# ethernet-phy.net
KiCad netlist of a schematic drawn in Altium Designer
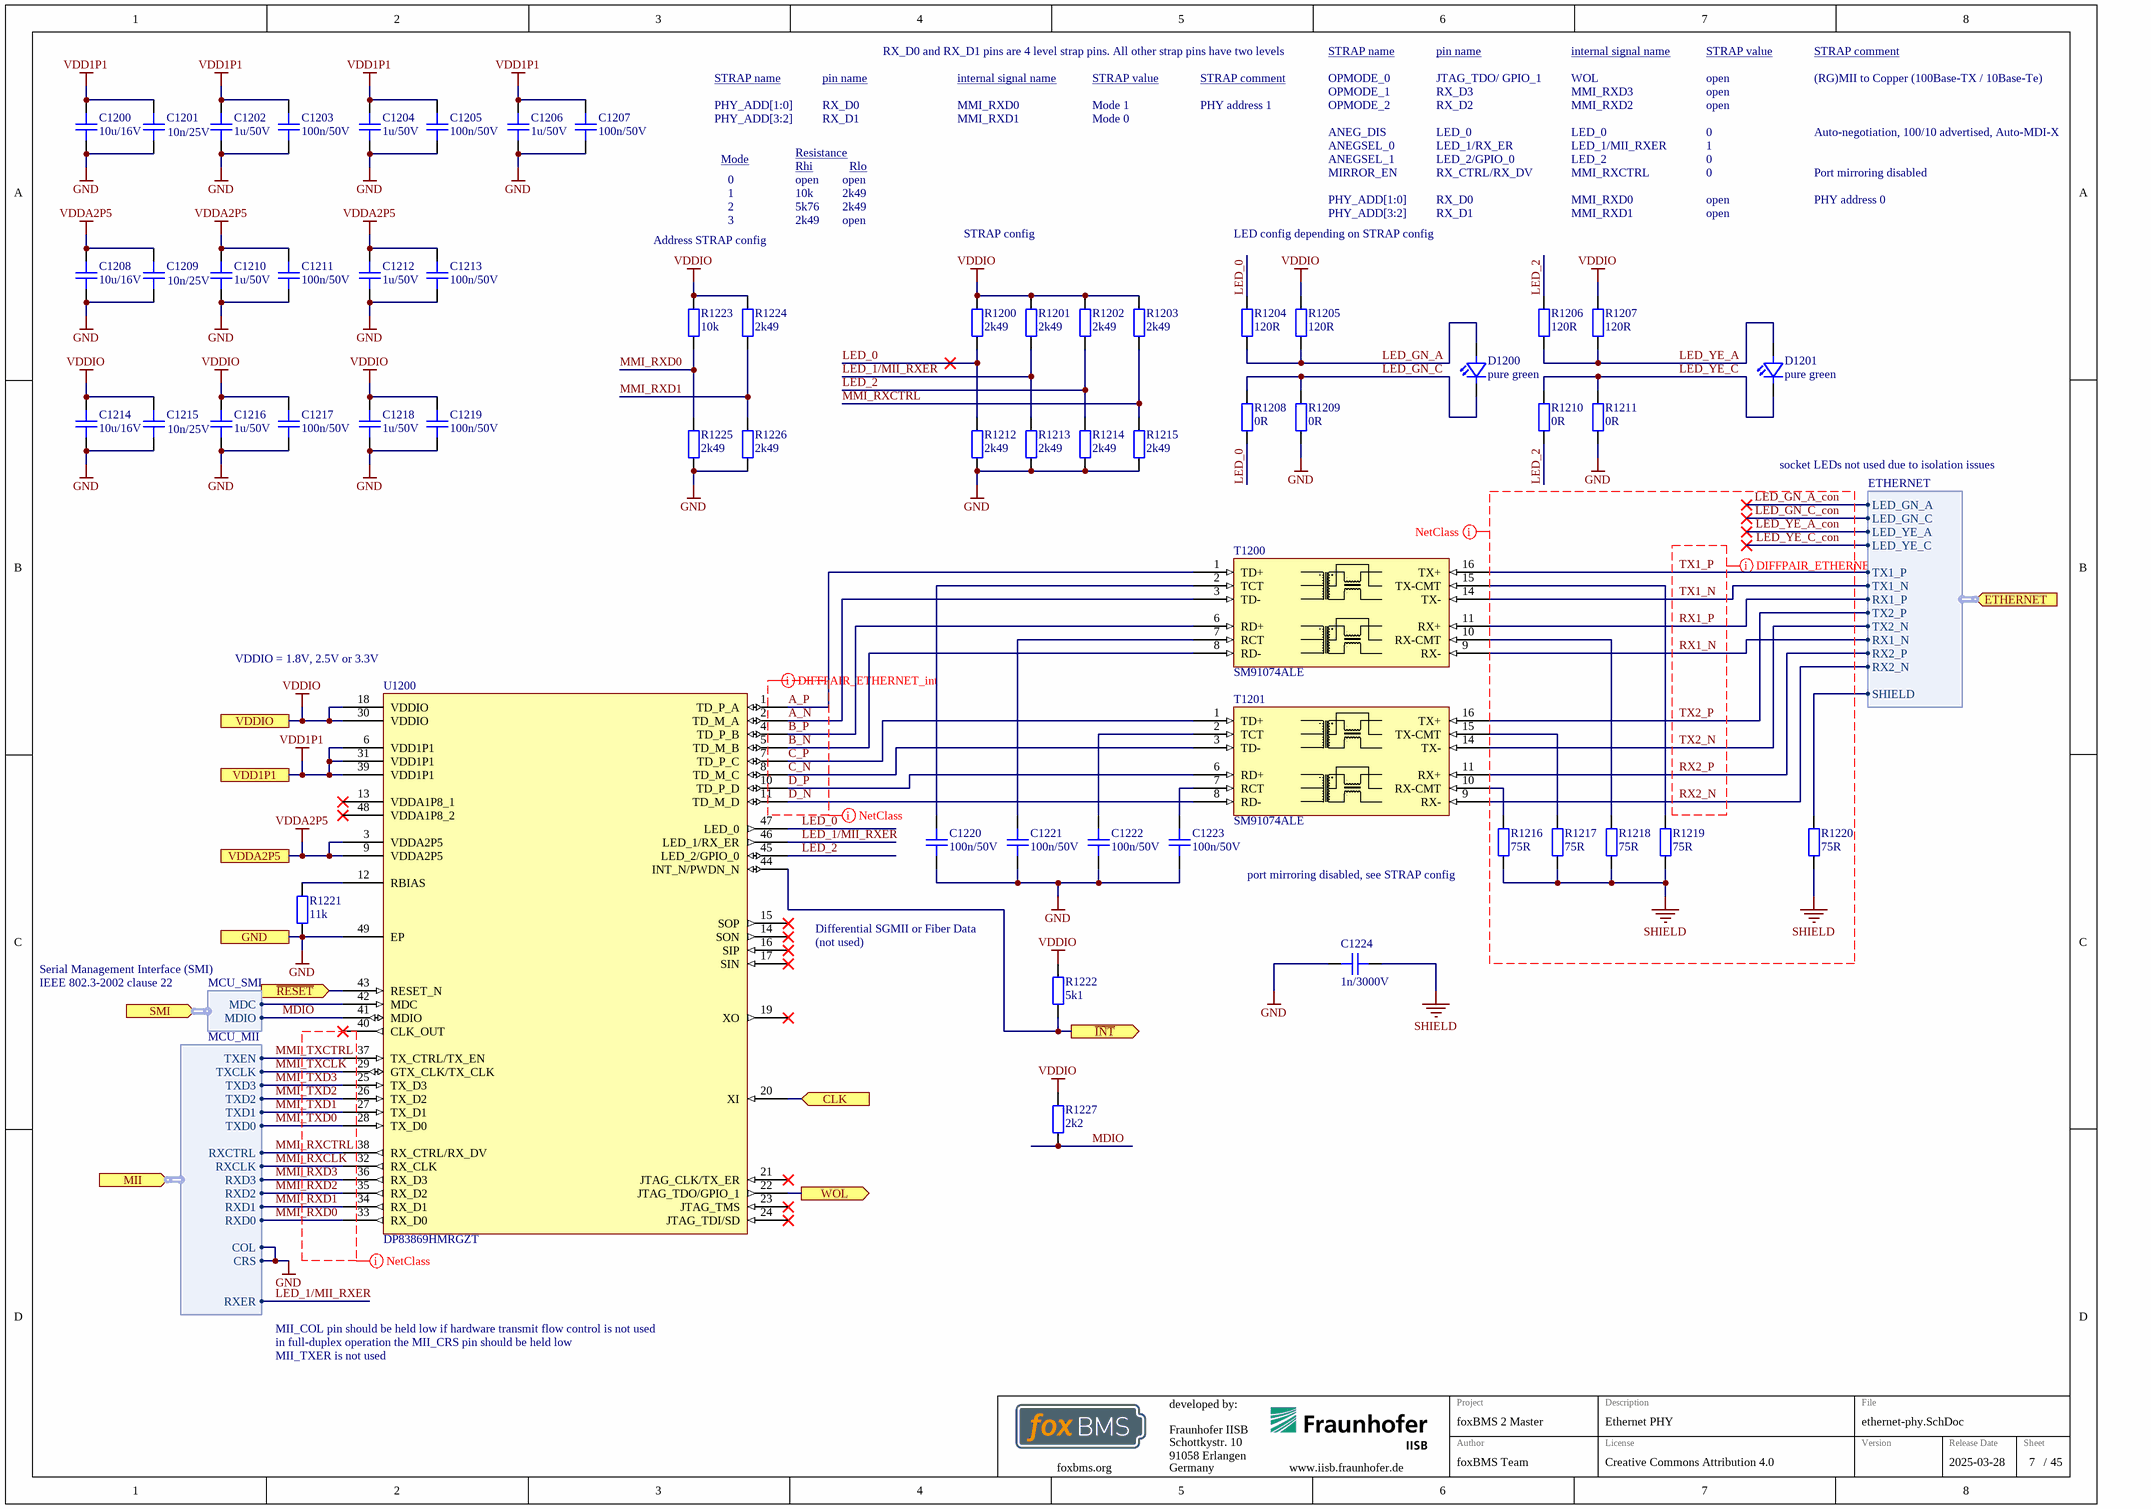
[diagram p0: ethernet-phy.SchDoc]

(export (version "E")
  (design (tool "Eeschema 10.0.6"))
  (components
    (comp (ref "C1200")
      (value "10u/16V")
      (footprint "CAPC2012X14N")
      (description "MLCC")
      (fields (field (name "PART NUMBER") "gen_C_ceramic_10u_16V_X7R_0805"))
      (libsource (lib "OE750") (part "C"))
    )
    (comp (ref "C1201")
      (value "10n/25V")
      (footprint "CAPC1005X06N")
      (description "MLCC")
      (fields (field (name "PART NUMBER") "gen_C_ceramic_10n_25V_X7R_0402"))
      (libsource (lib "OE750") (part "C"))
    )
    (comp (ref "C1202")
      (value "1u/50V")
      (footprint "CAPC1608X08N")
      (description "MLCC")
      (fields (field (name "PART NUMBER") "gen_C_ceramic_1u_50V_X7R_0603") (field (name "TOLERANCE") "± 10%"))
      (libsource (lib "OE750") (part "C"))
    )
    (comp (ref "C1203")
      (value "100n/50V")
      (footprint "CAPC1005X06N")
      (description "MLCC")
      (fields (field (name "PART NUMBER") "gen_C_ceramic_100n_50V_X7R_0402"))
      (libsource (lib "OE750") (part "C"))
    )
    (comp (ref "C1204")
      (value "1u/50V")
      (footprint "CAPC1608X08N")
      (description "MLCC")
      (fields (field (name "PART NUMBER") "gen_C_ceramic_1u_50V_X7R_0603") (field (name "TOLERANCE") "± 10%"))
      (libsource (lib "OE750") (part "C"))
    )
    (comp (ref "C1205")
      (value "100n/50V")
      (footprint "CAPC1005X06N")
      (description "MLCC")
      (fields (field (name "PART NUMBER") "gen_C_ceramic_100n_50V_X7R_0402"))
      (libsource (lib "OE750") (part "C"))
    )
    (comp (ref "C1206")
      (value "1u/50V")
      (footprint "CAPC1608X08N")
      (description "MLCC")
      (fields (field (name "PART NUMBER") "gen_C_ceramic_1u_50V_X7R_0603") (field (name "TOLERANCE") "± 10%"))
      (libsource (lib "OE750") (part "C"))
    )
    (comp (ref "C1207")
      (value "100n/50V")
      (footprint "CAPC1005X06N")
      (description "MLCC")
      (fields (field (name "PART NUMBER") "gen_C_ceramic_100n_50V_X7R_0402"))
      (libsource (lib "OE750") (part "C"))
    )
    (comp (ref "C1208")
      (value "10u/16V")
      (footprint "CAPC2012X14N")
      (description "MLCC")
      (fields (field (name "PART NUMBER") "gen_C_ceramic_10u_16V_X7R_0805"))
      (libsource (lib "OE750") (part "C"))
    )
    (comp (ref "C1209")
      (value "10n/25V")
      (footprint "CAPC1005X06N")
      (description "MLCC")
      (fields (field (name "PART NUMBER") "gen_C_ceramic_10n_25V_X7R_0402"))
      (libsource (lib "OE750") (part "C"))
    )
    (comp (ref "C1210")
      (value "1u/50V")
      (footprint "CAPC1608X08N")
      (description "MLCC")
      (fields (field (name "PART NUMBER") "gen_C_ceramic_1u_50V_X7R_0603") (field (name "TOLERANCE") "± 10%"))
      (libsource (lib "OE750") (part "C"))
    )
    (comp (ref "C1211")
      (value "100n/50V")
      (footprint "CAPC1005X06N")
      (description "MLCC")
      (fields (field (name "PART NUMBER") "gen_C_ceramic_100n_50V_X7R_0402"))
      (libsource (lib "OE750") (part "C"))
    )
    (comp (ref "C1212")
      (value "1u/50V")
      (footprint "CAPC1608X08N")
      (description "MLCC")
      (fields (field (name "PART NUMBER") "gen_C_ceramic_1u_50V_X7R_0603") (field (name "TOLERANCE") "± 10%"))
      (libsource (lib "OE750") (part "C"))
    )
    (comp (ref "C1213")
      (value "100n/50V")
      (footprint "CAPC1005X06N")
      (description "MLCC")
      (fields (field (name "PART NUMBER") "gen_C_ceramic_100n_50V_X7R_0402"))
      (libsource (lib "OE750") (part "C"))
    )
    (comp (ref "C1214")
      (value "10u/16V")
      (footprint "CAPC2012X14N")
      (description "MLCC")
      (fields (field (name "PART NUMBER") "gen_C_ceramic_10u_16V_X7R_0805"))
      (libsource (lib "OE750") (part "C"))
    )
    (comp (ref "C1215")
      (value "10n/25V")
      (footprint "CAPC1005X06N")
      (description "MLCC")
      (fields (field (name "PART NUMBER") "gen_C_ceramic_10n_25V_X7R_0402"))
      (libsource (lib "OE750") (part "C"))
    )
    (comp (ref "C1216")
      (value "1u/50V")
      (footprint "CAPC1608X08N")
      (description "MLCC")
      (fields (field (name "PART NUMBER") "gen_C_ceramic_1u_50V_X7R_0603") (field (name "TOLERANCE") "± 10%"))
      (libsource (lib "OE750") (part "C"))
    )
    (comp (ref "C1217")
      (value "100n/50V")
      (footprint "CAPC1005X06N")
      (description "MLCC")
      (fields (field (name "PART NUMBER") "gen_C_ceramic_100n_50V_X7R_0402"))
      (libsource (lib "OE750") (part "C"))
    )
    (comp (ref "C1218")
      (value "1u/50V")
      (footprint "CAPC1608X08N")
      (description "MLCC")
      (fields (field (name "PART NUMBER") "gen_C_ceramic_1u_50V_X7R_0603") (field (name "TOLERANCE") "± 10%"))
      (libsource (lib "OE750") (part "C"))
    )
    (comp (ref "C1219")
      (value "100n/50V")
      (footprint "CAPC1005X06N")
      (description "MLCC")
      (fields (field (name "PART NUMBER") "gen_C_ceramic_100n_50V_X7R_0402"))
      (libsource (lib "OE750") (part "C"))
    )
    (comp (ref "C1220")
      (value "100n/50V")
      (footprint "CAPC1005X06N")
      (description "MLCC")
      (fields (field (name "PART NUMBER") "gen_C_ceramic_100n_50V_X7R_0402"))
      (libsource (lib "OE750") (part "C"))
    )
    (comp (ref "C1221")
      (value "100n/50V")
      (footprint "CAPC1005X06N")
      (description "MLCC")
      (fields (field (name "PART NUMBER") "gen_C_ceramic_100n_50V_X7R_0402"))
      (libsource (lib "OE750") (part "C"))
    )
    (comp (ref "C1222")
      (value "100n/50V")
      (footprint "CAPC1005X06N")
      (description "MLCC")
      (fields (field (name "PART NUMBER") "gen_C_ceramic_100n_50V_X7R_0402"))
      (libsource (lib "OE750") (part "C"))
    )
    (comp (ref "C1223")
      (value "100n/50V")
      (footprint "CAPC1005X06N")
      (description "MLCC")
      (fields (field (name "PART NUMBER") "gen_C_ceramic_100n_50V_X7R_0402"))
      (libsource (lib "OE750") (part "C"))
    )
    (comp (ref "C1224")
      (value "1n/3000V")
      (footprint "CAPC2220(5750)230_N")
      (description "MLCC")
      (fields (field (name "PART NUMBER") "gen_C_ceramic_1n_3000V_X7R_2220"))
      (libsource (lib "OE750") (part "C"))
    )
    (comp (ref "D1200")
      (value "pure green")
      (footprint "LEDC1608X07N")
      (description "TLMP1100-GS08")
      (fields (field (name "PART NUMBER") "LED_0603_pure_green_AECQ") (field (name "MANUFACTURER") "Vishay"))
      (libsource (lib "OE750") (part "D_LED"))
    )
    (comp (ref "D1201")
      (value "pure green")
      (footprint "LEDC1608X07N")
      (description "TLMP1100-GS08")
      (fields (field (name "PART NUMBER") "LED_0603_pure_green_AECQ") (field (name "MANUFACTURER") "Vishay"))
      (libsource (lib "OE750") (part "D_LED"))
    )
    (comp (ref "R1200")
      (value "2k49")
      (footprint "RESC1005X04N")
      (description "SMD Resistor 2k49 0402")
      (fields (field (name "PART NUMBER") "gen_R_2k49_0402") (field (name "TOLERANCE") "1%"))
      (libsource (lib "OE750") (part "R"))
    )
    (comp (ref "R1201")
      (value "2k49")
      (footprint "RESC1005X04N")
      (description "SMD Resistor 2k49 0402")
      (fields (field (name "PART NUMBER") "gen_R_2k49_0402") (field (name "TOLERANCE") "1%"))
      (libsource (lib "OE750") (part "R"))
    )
    (comp (ref "R1202")
      (value "2k49")
      (footprint "RESC1005X04N")
      (description "SMD Resistor 2k49 0402")
      (fields (field (name "PART NUMBER") "gen_R_2k49_0402") (field (name "TOLERANCE") "1%"))
      (libsource (lib "OE750") (part "R"))
    )
    (comp (ref "R1203")
      (value "2k49")
      (footprint "RESC1005X04N")
      (description "SMD Resistor 2k49 0402")
      (fields (field (name "PART NUMBER") "gen_R_2k49_0402") (field (name "TOLERANCE") "1%"))
      (libsource (lib "OE750") (part "R"))
    )
    (comp (ref "R1204")
      (value "120R")
      (footprint "RESC1005X04N")
      (description "SMD Resistor 120R 0402")
      (fields (field (name "PART NUMBER") "gen_R_120R_0402") (field (name "TOLERANCE") "1%"))
      (libsource (lib "OE750") (part "R"))
    )
    (comp (ref "R1205")
      (value "120R")
      (footprint "RESC1005X04N")
      (description "SMD Resistor 120R 0402")
      (fields (field (name "PART NUMBER") "gen_R_120R_0402") (field (name "TOLERANCE") "1%"))
      (libsource (lib "OE750") (part "R"))
    )
    (comp (ref "R1206")
      (value "120R")
      (footprint "RESC1005X04N")
      (description "SMD Resistor 120R 0402")
      (fields (field (name "PART NUMBER") "gen_R_120R_0402") (field (name "TOLERANCE") "1%"))
      (libsource (lib "OE750") (part "R"))
    )
    (comp (ref "R1207")
      (value "120R")
      (footprint "RESC1005X04N")
      (description "SMD Resistor 120R 0402")
      (fields (field (name "PART NUMBER") "gen_R_120R_0402") (field (name "TOLERANCE") "1%"))
      (libsource (lib "OE750") (part "R"))
    )
    (comp (ref "R1208")
      (value "0R")
      (footprint "RESC1005X04N")
      (description "SMD Resistor 0R 0402")
      (fields (field (name "PART NUMBER") "gen_R_0R_0402") (field (name "POWER") "0.063W"))
      (libsource (lib "OE750") (part "R"))
    )
    (comp (ref "R1209")
      (value "0R")
      (footprint "RESC1005X04N")
      (description "SMD Resistor 0R 0402")
      (fields (field (name "PART NUMBER") "gen_R_0R_0402") (field (name "POWER") "0.063W"))
      (libsource (lib "OE750") (part "R"))
    )
    (comp (ref "R1210")
      (value "0R")
      (footprint "RESC1005X04N")
      (description "SMD Resistor 0R 0402")
      (fields (field (name "PART NUMBER") "gen_R_0R_0402") (field (name "POWER") "0.063W"))
      (libsource (lib "OE750") (part "R"))
    )
    (comp (ref "R1211")
      (value "0R")
      (footprint "RESC1005X04N")
      (description "SMD Resistor 0R 0402")
      (fields (field (name "PART NUMBER") "gen_R_0R_0402") (field (name "POWER") "0.063W"))
      (libsource (lib "OE750") (part "R"))
    )
    (comp (ref "R1212")
      (value "2k49")
      (footprint "RESC1005X04N")
      (description "SMD Resistor 2k49 0402")
      (fields (field (name "PART NUMBER") "gen_R_2k49_0402") (field (name "TOLERANCE") "1%"))
      (libsource (lib "OE750") (part "R"))
    )
    (comp (ref "R1213")
      (value "2k49")
      (footprint "RESC1005X04N")
      (description "SMD Resistor 2k49 0402")
      (fields (field (name "PART NUMBER") "gen_R_2k49_0402") (field (name "TOLERANCE") "1%"))
      (libsource (lib "OE750") (part "R"))
    )
    (comp (ref "R1214")
      (value "2k49")
      (footprint "RESC1005X04N")
      (description "SMD Resistor 2k49 0402")
      (fields (field (name "PART NUMBER") "gen_R_2k49_0402") (field (name "TOLERANCE") "1%"))
      (libsource (lib "OE750") (part "R"))
    )
    (comp (ref "R1215")
      (value "2k49")
      (footprint "RESC1005X04N")
      (description "SMD Resistor 2k49 0402")
      (fields (field (name "PART NUMBER") "gen_R_2k49_0402") (field (name "TOLERANCE") "1%"))
      (libsource (lib "OE750") (part "R"))
    )
    (comp (ref "R1216")
      (value "75R")
      (footprint "RESC1005X04N")
      (description "SMD Resistor 75R 0402")
      (fields (field (name "PART NUMBER") "gen_R_75R_0402") (field (name "TOLERANCE") "1%"))
      (libsource (lib "OE750") (part "R"))
    )
    (comp (ref "R1217")
      (value "75R")
      (footprint "RESC1005X04N")
      (description "SMD Resistor 75R 0402")
      (fields (field (name "PART NUMBER") "gen_R_75R_0402") (field (name "TOLERANCE") "1%"))
      (libsource (lib "OE750") (part "R"))
    )
    (comp (ref "R1218")
      (value "75R")
      (footprint "RESC1005X04N")
      (description "SMD Resistor 75R 0402")
      (fields (field (name "PART NUMBER") "gen_R_75R_0402") (field (name "TOLERANCE") "1%"))
      (libsource (lib "OE750") (part "R"))
    )
    (comp (ref "R1219")
      (value "75R")
      (footprint "RESC1005X04N")
      (description "SMD Resistor 75R 0402")
      (fields (field (name "PART NUMBER") "gen_R_75R_0402") (field (name "TOLERANCE") "1%"))
      (libsource (lib "OE750") (part "R"))
    )
    (comp (ref "R1220")
      (value "75R")
      (footprint "RESC1005X04N")
      (description "SMD Resistor 75R 0402")
      (fields (field (name "PART NUMBER") "gen_R_75R_0402") (field (name "TOLERANCE") "1%"))
      (libsource (lib "OE750") (part "R"))
    )
    (comp (ref "R1221")
      (value "11k")
      (footprint "RESC1005X04N")
      (description "SMD Resistor 11k 0402")
      (fields (field (name "PART NUMBER") "gen_R_11k_0402") (field (name "TOLERANCE") "1%"))
      (libsource (lib "OE750") (part "R"))
    )
    (comp (ref "R1222")
      (value "5k1")
      (footprint "RESC1005X04N")
      (description "SMD Resistor 5k1 0402")
      (fields (field (name "PART NUMBER") "gen_R_5k1_0402") (field (name "TOLERANCE") "1%"))
      (libsource (lib "OE750") (part "R"))
    )
    (comp (ref "R1223")
      (value "10k")
      (footprint "RESC1005X04N")
      (description "SMD Resistor 10k 0402")
      (fields (field (name "PART NUMBER") "gen_R_10k_0402") (field (name "TOLERANCE") "1%"))
      (libsource (lib "OE750") (part "R"))
    )
    (comp (ref "R1224")
      (value "2k49")
      (footprint "RESC1005X04N")
      (description "SMD Resistor 2k49 0402")
      (fields (field (name "PART NUMBER") "gen_R_2k49_0402") (field (name "TOLERANCE") "1%"))
      (libsource (lib "OE750") (part "R"))
    )
    (comp (ref "R1225")
      (value "2k49")
      (footprint "RESC1005X04N")
      (description "SMD Resistor 2k49 0402")
      (fields (field (name "PART NUMBER") "gen_R_2k49_0402") (field (name "TOLERANCE") "1%"))
      (libsource (lib "OE750") (part "R"))
    )
    (comp (ref "R1226")
      (value "2k49")
      (footprint "RESC1005X04N")
      (description "SMD Resistor 2k49 0402")
      (fields (field (name "PART NUMBER") "gen_R_2k49_0402") (field (name "TOLERANCE") "1%"))
      (libsource (lib "OE750") (part "R"))
    )
    (comp (ref "R1227")
      (value "2k2")
      (footprint "RESC1005X04N")
      (description "SMD Resistor 2k2 0402")
      (fields (field (name "PART NUMBER") "gen_R_2k2_0402") (field (name "TOLERANCE") "1%"))
      (libsource (lib "OE750") (part "R"))
    )
    (comp (ref "T1200")
      (value "SM91074ALE")
      (footprint "SM91074ALE")
      (description "10/100 Base-T Transformer")
      (fields (field (name "MANUFACTURER") "Bourns"))
      (libsource (lib "OE750") (part "SM91074ALE"))
    )
    (comp (ref "T1201")
      (value "SM91074ALE")
      (footprint "SM91074ALE")
      (description "10/100 Base-T Transformer")
      (fields (field (name "MANUFACTURER") "Bourns"))
      (libsource (lib "OE750") (part "SM91074ALE"))
    )
    (comp (ref "U1200")
      (value "DP83869HMRGZT")
      (footprint "DP83869HM-RGZ")
      (description "High Immunity 10/100/1000 Ethernet Physical Layer Transceiver and Fiber Interface")
      (fields (field (name "MANUFACTURER") "Texas Instruments"))
      (libsource (lib "OE750") (part "DP83869HM"))
    )
  )
  (nets
    (net (code "4") (name "/A_N") (class "Default")
      (node (ref "T1200") (pin "3") (pinfunction "TD-_3") (pintype "input"))
      (node (ref "U1200") (pin "2") (pinfunction "TD_M_A_2") (pintype "bidirectional"))
    )
    (net (code "5") (name "/A_P") (class "Default")
      (node (ref "T1200") (pin "1") (pinfunction "TD+_1") (pintype "input"))
      (node (ref "U1200") (pin "1") (pinfunction "TD_P_A_1") (pintype "bidirectional"))
    )
    (net (code "6") (name "/B_N") (class "Default")
      (node (ref "T1200") (pin "8") (pinfunction "RD-_8") (pintype "input"))
      (node (ref "U1200") (pin "5") (pinfunction "TD_M_B_5") (pintype "bidirectional"))
    )
    (net (code "7") (name "/B_P") (class "Default")
      (node (ref "T1200") (pin "6") (pinfunction "RD+_6") (pintype "input"))
      (node (ref "U1200") (pin "4") (pinfunction "TD_P_B_4") (pintype "bidirectional"))
    )
    (net (code "8") (name "/CLK") (class "Default")
      (node (ref "U1200") (pin "20") (pinfunction "XI_20") (pintype "input"))
    )
    (net (code "9") (name "/C_N") (class "Default")
      (node (ref "T1201") (pin "3") (pinfunction "TD-_3") (pintype "input"))
      (node (ref "U1200") (pin "8") (pinfunction "TD_M_C_8") (pintype "bidirectional"))
    )
    (net (code "10") (name "/C_P") (class "Default")
      (node (ref "T1201") (pin "1") (pinfunction "TD+_1") (pintype "input"))
      (node (ref "U1200") (pin "7") (pinfunction "TD_P_C_7") (pintype "bidirectional"))
    )
    (net (code "11") (name "/D_N") (class "Default")
      (node (ref "T1201") (pin "8") (pinfunction "RD-_8") (pintype "input"))
      (node (ref "U1200") (pin "11") (pinfunction "TD_M_D_11") (pintype "bidirectional"))
    )
    (net (code "12") (name "/D_P") (class "Default")
      (node (ref "T1201") (pin "6") (pinfunction "RD+_6") (pintype "input"))
      (node (ref "U1200") (pin "10") (pinfunction "TD_P_D_10") (pintype "bidirectional"))
    )
    (net (code "13") (name "/INT") (class "Default")
      (node (ref "R1222") (pin "1") (pinfunction "1_1") (pintype "passive"))
      (node (ref "U1200") (pin "44") (pinfunction "INT_N/PWDN_N_44") (pintype "bidirectional"))
    )
    (net (code "14") (name "/LED_0") (class "Default")
      (node (ref "R1200") (pin "1") (pinfunction "1_1") (pintype "passive"))
      (node (ref "R1204") (pin "2") (pinfunction "2_2") (pintype "passive"))
      (node (ref "R1208") (pin "1") (pinfunction "1_1") (pintype "passive"))
      (node (ref "R1212") (pin "2") (pinfunction "2_2") (pintype "passive"))
      (node (ref "U1200") (pin "47") (pinfunction "LED_0_47") (pintype "output"))
    )
    (net (code "15") (name "/LED_1{slash}MII_RXER") (class "Default")
      (node (ref "R1201") (pin "1") (pinfunction "1_1") (pintype "passive"))
      (node (ref "R1213") (pin "2") (pinfunction "2_2") (pintype "passive"))
      (node (ref "U1200") (pin "46") (pinfunction "LED_1/RX_ER_46") (pintype "output"))
    )
    (net (code "16") (name "/LED_2") (class "Default")
      (node (ref "R1202") (pin "1") (pinfunction "1_1") (pintype "passive"))
      (node (ref "R1206") (pin "2") (pinfunction "2_2") (pintype "passive"))
      (node (ref "R1210") (pin "1") (pinfunction "1_1") (pintype "passive"))
      (node (ref "R1214") (pin "2") (pinfunction "2_2") (pintype "passive"))
      (node (ref "U1200") (pin "45") (pinfunction "LED_2/GPIO_0_45") (pintype "bidirectional"))
    )
    (net (code "17") (name "/LED_GN_A") (class "Default")
      (node (ref "D1200") (pin "2") (pinfunction "A_2") (pintype "passive"))
      (node (ref "R1204") (pin "1") (pinfunction "1_1") (pintype "passive"))
      (node (ref "R1205") (pin "1") (pinfunction "1_1") (pintype "passive"))
    )
    (net (code "19") (name "/LED_GN_C") (class "Default")
      (node (ref "D1200") (pin "1") (pinfunction "C_1") (pintype "passive"))
      (node (ref "R1208") (pin "2") (pinfunction "2_2") (pintype "passive"))
      (node (ref "R1209") (pin "2") (pinfunction "2_2") (pintype "passive"))
    )
    (net (code "21") (name "/LED_YE_A") (class "Default")
      (node (ref "D1201") (pin "2") (pinfunction "A_2") (pintype "passive"))
      (node (ref "R1206") (pin "1") (pinfunction "1_1") (pintype "passive"))
      (node (ref "R1207") (pin "1") (pinfunction "1_1") (pintype "passive"))
    )
    (net (code "23") (name "/LED_YE_C") (class "Default")
      (node (ref "D1201") (pin "1") (pinfunction "C_1") (pintype "passive"))
      (node (ref "R1210") (pin "2") (pinfunction "2_2") (pintype "passive"))
      (node (ref "R1211") (pin "2") (pinfunction "2_2") (pintype "passive"))
    )
    (net (code "25") (name "/MDC") (class "Default")
      (node (ref "U1200") (pin "42") (pinfunction "MDC_42") (pintype "input"))
    )
    (net (code "26") (name "/MDIO") (class "Default")
      (node (ref "R1227") (pin "1") (pinfunction "1_1") (pintype "passive"))
      (node (ref "U1200") (pin "41") (pinfunction "MDIO_41") (pintype "bidirectional"))
    )
    (net (code "27") (name "/MMI_RXCLK") (class "Default")
      (node (ref "U1200") (pin "32") (pinfunction "RX_CLK_32") (pintype "output"))
    )
    (net (code "28") (name "/MMI_RXCTRL") (class "Default")
      (node (ref "R1203") (pin "1") (pinfunction "1_1") (pintype "passive"))
      (node (ref "R1215") (pin "2") (pinfunction "2_2") (pintype "passive"))
      (node (ref "U1200") (pin "38") (pinfunction "RX_CTRL/RX_DV_38") (pintype "output"))
    )
    (net (code "29") (name "/MMI_RXD0") (class "Default")
      (node (ref "R1223") (pin "1") (pinfunction "1_1") (pintype "passive"))
      (node (ref "R1225") (pin "2") (pinfunction "2_2") (pintype "passive"))
      (node (ref "U1200") (pin "33") (pinfunction "RX_D0_33") (pintype "output"))
    )
    (net (code "30") (name "/MMI_RXD1") (class "Default")
      (node (ref "R1224") (pin "1") (pinfunction "1_1") (pintype "passive"))
      (node (ref "R1226") (pin "2") (pinfunction "2_2") (pintype "passive"))
      (node (ref "U1200") (pin "34") (pinfunction "RX_D1_34") (pintype "output"))
    )
    (net (code "31") (name "/MMI_RXD2") (class "Default")
      (node (ref "U1200") (pin "35") (pinfunction "RX_D2_35") (pintype "output"))
    )
    (net (code "32") (name "/MMI_RXD3") (class "Default")
      (node (ref "U1200") (pin "36") (pinfunction "RX_D3_36") (pintype "output"))
    )
    (net (code "33") (name "/MMI_TXCLK") (class "Default")
      (node (ref "U1200") (pin "29") (pinfunction "GTX_CLK/TX_CLK_29") (pintype "bidirectional"))
    )
    (net (code "34") (name "/MMI_TXCTRL") (class "Default")
      (node (ref "U1200") (pin "37") (pinfunction "TX_CTRL/TX_EN_37") (pintype "input"))
    )
    (net (code "35") (name "/MMI_TXD0") (class "Default")
      (node (ref "U1200") (pin "28") (pinfunction "TX_D0_28") (pintype "input"))
    )
    (net (code "36") (name "/MMI_TXD1") (class "Default")
      (node (ref "U1200") (pin "27") (pinfunction "TX_D1_27") (pintype "input"))
    )
    (net (code "37") (name "/MMI_TXD2") (class "Default")
      (node (ref "U1200") (pin "26") (pinfunction "TX_D2_26") (pintype "input"))
    )
    (net (code "38") (name "/MMI_TXD3") (class "Default")
      (node (ref "U1200") (pin "25") (pinfunction "TX_D3_25") (pintype "input"))
    )
    (net (code "39") (name "/RESET") (class "Default")
      (node (ref "U1200") (pin "43") (pinfunction "RESET_N_43") (pintype "input"))
    )
    (net (code "40") (name "/RX1_N") (class "Default")
      (node (ref "T1200") (pin "9") (pinfunction "RX-_9") (pintype "input"))
    )
    (net (code "41") (name "/RX1_P") (class "Default")
      (node (ref "T1200") (pin "11") (pinfunction "RX+_11") (pintype "input"))
    )
    (net (code "42") (name "/RX2_N") (class "Default")
      (node (ref "T1201") (pin "9") (pinfunction "RX-_9") (pintype "input"))
    )
    (net (code "43") (name "/RX2_P") (class "Default")
      (node (ref "T1201") (pin "11") (pinfunction "RX+_11") (pintype "input"))
    )
    (net (code "44") (name "/TX1_N") (class "Default")
      (node (ref "T1200") (pin "14") (pinfunction "TX-_14") (pintype "input"))
    )
    (net (code "45") (name "/TX1_P") (class "Default")
      (node (ref "T1200") (pin "16") (pinfunction "TX+_16") (pintype "input"))
    )
    (net (code "46") (name "/TX2_N") (class "Default")
      (node (ref "T1201") (pin "14") (pinfunction "TX-_14") (pintype "input"))
    )
    (net (code "47") (name "/TX2_P") (class "Default")
      (node (ref "T1201") (pin "16") (pinfunction "TX+_16") (pintype "input"))
    )
    (net (code "48") (name "/WOL") (class "Default")
      (node (ref "U1200") (pin "22") (pinfunction "JTAG_TDO/GPIO_1_22") (pintype "output"))
    )
    (net (code "52") (name "GND") (class "Default")
      (node (ref "C1200") (pin "1") (pinfunction "1_1") (pintype "passive"))
      (node (ref "C1201") (pin "1") (pinfunction "1_1") (pintype "passive"))
      (node (ref "C1202") (pin "1") (pinfunction "1_1") (pintype "passive"))
      (node (ref "C1203") (pin "1") (pinfunction "1_1") (pintype "passive"))
      (node (ref "C1204") (pin "1") (pinfunction "1_1") (pintype "passive"))
      (node (ref "C1205") (pin "1") (pinfunction "1_1") (pintype "passive"))
      (node (ref "C1206") (pin "1") (pinfunction "1_1") (pintype "passive"))
      (node (ref "C1207") (pin "1") (pinfunction "1_1") (pintype "passive"))
      (node (ref "C1208") (pin "1") (pinfunction "1_1") (pintype "passive"))
      (node (ref "C1209") (pin "1") (pinfunction "1_1") (pintype "passive"))
      (node (ref "C1210") (pin "1") (pinfunction "1_1") (pintype "passive"))
      (node (ref "C1211") (pin "1") (pinfunction "1_1") (pintype "passive"))
      (node (ref "C1212") (pin "1") (pinfunction "1_1") (pintype "passive"))
      (node (ref "C1213") (pin "1") (pinfunction "1_1") (pintype "passive"))
      (node (ref "C1214") (pin "1") (pinfunction "1_1") (pintype "passive"))
      (node (ref "C1215") (pin "1") (pinfunction "1_1") (pintype "passive"))
      (node (ref "C1216") (pin "1") (pinfunction "1_1") (pintype "passive"))
      (node (ref "C1217") (pin "1") (pinfunction "1_1") (pintype "passive"))
      (node (ref "C1218") (pin "1") (pinfunction "1_1") (pintype "passive"))
      (node (ref "C1219") (pin "1") (pinfunction "1_1") (pintype "passive"))
      (node (ref "C1220") (pin "1") (pinfunction "1_1") (pintype "passive"))
      (node (ref "C1221") (pin "1") (pinfunction "1_1") (pintype "passive"))
      (node (ref "C1222") (pin "1") (pinfunction "1_1") (pintype "passive"))
      (node (ref "C1223") (pin "1") (pinfunction "1_1") (pintype "passive"))
      (node (ref "C1224") (pin "1") (pinfunction "1_1") (pintype "passive"))
      (node (ref "R1209") (pin "1") (pinfunction "1_1") (pintype "passive"))
      (node (ref "R1211") (pin "1") (pinfunction "1_1") (pintype "passive"))
      (node (ref "R1212") (pin "1") (pinfunction "1_1") (pintype "passive"))
      (node (ref "R1213") (pin "1") (pinfunction "1_1") (pintype "passive"))
      (node (ref "R1214") (pin "1") (pinfunction "1_1") (pintype "passive"))
      (node (ref "R1215") (pin "1") (pinfunction "1_1") (pintype "passive"))
      (node (ref "R1221") (pin "1") (pinfunction "1_1") (pintype "passive"))
      (node (ref "R1225") (pin "1") (pinfunction "1_1") (pintype "passive"))
      (node (ref "R1226") (pin "1") (pinfunction "1_1") (pintype "passive"))
      (node (ref "U1200") (pin "49") (pinfunction "EP_49") (pintype "power_in"))
    )
    (net (code "53") (name "Net-(T1200-RCT)") (class "Default")
      (node (ref "C1221") (pin "2") (pinfunction "2_2") (pintype "passive"))
      (node (ref "T1200") (pin "7") (pinfunction "RCT_7") (pintype "input"))
    )
    (net (code "54") (name "Net-(T1200-RX-CMT)") (class "Default")
      (node (ref "R1218") (pin "2") (pinfunction "2_2") (pintype "passive"))
      (node (ref "T1200") (pin "10") (pinfunction "RX-CMT_10") (pintype "input"))
    )
    (net (code "55") (name "Net-(T1200-TCT)") (class "Default")
      (node (ref "C1220") (pin "2") (pinfunction "2_2") (pintype "passive"))
      (node (ref "T1200") (pin "2") (pinfunction "TCT_2") (pintype "input"))
    )
    (net (code "56") (name "Net-(T1200-TX-CMT)") (class "Default")
      (node (ref "R1219") (pin "2") (pinfunction "2_2") (pintype "passive"))
      (node (ref "T1200") (pin "15") (pinfunction "TX-CMT_15") (pintype "input"))
    )
    (net (code "57") (name "Net-(T1201-RCT)") (class "Default")
      (node (ref "C1223") (pin "2") (pinfunction "2_2") (pintype "passive"))
      (node (ref "T1201") (pin "7") (pinfunction "RCT_7") (pintype "input"))
    )
    (net (code "58") (name "Net-(T1201-RX-CMT)") (class "Default")
      (node (ref "R1216") (pin "2") (pinfunction "2_2") (pintype "passive"))
      (node (ref "T1201") (pin "10") (pinfunction "RX-CMT_10") (pintype "input"))
    )
    (net (code "59") (name "Net-(T1201-TCT)") (class "Default")
      (node (ref "C1222") (pin "2") (pinfunction "2_2") (pintype "passive"))
      (node (ref "T1201") (pin "2") (pinfunction "TCT_2") (pintype "input"))
    )
    (net (code "60") (name "Net-(T1201-TX-CMT)") (class "Default")
      (node (ref "R1217") (pin "2") (pinfunction "2_2") (pintype "passive"))
      (node (ref "T1201") (pin "15") (pinfunction "TX-CMT_15") (pintype "input"))
    )
    (net (code "61") (name "Net-(U1200-RBIAS)") (class "Default")
      (node (ref "R1221") (pin "2") (pinfunction "2_2") (pintype "passive"))
      (node (ref "U1200") (pin "12") (pinfunction "RBIAS_12") (pintype "passive"))
    )
    (net (code "62") (name "SHIELD") (class "Default")
      (node (ref "C1224") (pin "2") (pinfunction "2_2") (pintype "passive"))
      (node (ref "R1216") (pin "1") (pinfunction "1_1") (pintype "passive"))
      (node (ref "R1217") (pin "1") (pinfunction "1_1") (pintype "passive"))
      (node (ref "R1218") (pin "1") (pinfunction "1_1") (pintype "passive"))
      (node (ref "R1219") (pin "1") (pinfunction "1_1") (pintype "passive"))
      (node (ref "R1220") (pin "1") (pinfunction "1_1") (pintype "passive"))
    )
    (net (code "63") (name "VDD1P1") (class "Default")
      (node (ref "C1200") (pin "2") (pinfunction "2_2") (pintype "passive"))
      (node (ref "C1201") (pin "2") (pinfunction "2_2") (pintype "passive"))
      (node (ref "C1202") (pin "2") (pinfunction "2_2") (pintype "passive"))
      (node (ref "C1203") (pin "2") (pinfunction "2_2") (pintype "passive"))
      (node (ref "C1204") (pin "2") (pinfunction "2_2") (pintype "passive"))
      (node (ref "C1205") (pin "2") (pinfunction "2_2") (pintype "passive"))
      (node (ref "C1206") (pin "2") (pinfunction "2_2") (pintype "passive"))
      (node (ref "C1207") (pin "2") (pinfunction "2_2") (pintype "passive"))
      (node (ref "U1200") (pin "31") (pinfunction "VDD1P1_31") (pintype "power_in"))
      (node (ref "U1200") (pin "39") (pinfunction "VDD1P1_39") (pintype "power_in"))
      (node (ref "U1200") (pin "6") (pinfunction "VDD1P1_6") (pintype "power_in"))
    )
    (net (code "64") (name "VDDA2P5") (class "Default")
      (node (ref "C1208") (pin "2") (pinfunction "2_2") (pintype "passive"))
      (node (ref "C1209") (pin "2") (pinfunction "2_2") (pintype "passive"))
      (node (ref "C1210") (pin "2") (pinfunction "2_2") (pintype "passive"))
      (node (ref "C1211") (pin "2") (pinfunction "2_2") (pintype "passive"))
      (node (ref "C1212") (pin "2") (pinfunction "2_2") (pintype "passive"))
      (node (ref "C1213") (pin "2") (pinfunction "2_2") (pintype "passive"))
      (node (ref "U1200") (pin "3") (pinfunction "VDDA2P5_3") (pintype "power_in"))
      (node (ref "U1200") (pin "9") (pinfunction "VDDA2P5_9") (pintype "power_in"))
    )
    (net (code "65") (name "VDDIO") (class "Default")
      (node (ref "C1214") (pin "2") (pinfunction "2_2") (pintype "passive"))
      (node (ref "C1215") (pin "2") (pinfunction "2_2") (pintype "passive"))
      (node (ref "C1216") (pin "2") (pinfunction "2_2") (pintype "passive"))
      (node (ref "C1217") (pin "2") (pinfunction "2_2") (pintype "passive"))
      (node (ref "C1218") (pin "2") (pinfunction "2_2") (pintype "passive"))
      (node (ref "C1219") (pin "2") (pinfunction "2_2") (pintype "passive"))
      (node (ref "R1200") (pin "2") (pinfunction "2_2") (pintype "passive"))
      (node (ref "R1201") (pin "2") (pinfunction "2_2") (pintype "passive"))
      (node (ref "R1202") (pin "2") (pinfunction "2_2") (pintype "passive"))
      (node (ref "R1203") (pin "2") (pinfunction "2_2") (pintype "passive"))
      (node (ref "R1205") (pin "2") (pinfunction "2_2") (pintype "passive"))
      (node (ref "R1207") (pin "2") (pinfunction "2_2") (pintype "passive"))
      (node (ref "R1222") (pin "2") (pinfunction "2_2") (pintype "passive"))
      (node (ref "R1223") (pin "2") (pinfunction "2_2") (pintype "passive"))
      (node (ref "R1224") (pin "2") (pinfunction "2_2") (pintype "passive"))
      (node (ref "R1227") (pin "2") (pinfunction "2_2") (pintype "passive"))
      (node (ref "U1200") (pin "18") (pinfunction "VDDIO_18") (pintype "power_in"))
      (node (ref "U1200") (pin "30") (pinfunction "VDDIO_30") (pintype "power_in"))
    )
    (net (code "66") (name "unconnected-(R1220-Pad2)") (class "Default")
      (node (ref "R1220") (pin "2") (pinfunction "2_2") (pintype "passive"))
    )
    (net (code "67") (name "unconnected-(U1200-CLK_OUT-Pad40)") (class "Default")
      (node (ref "U1200") (pin "40") (pinfunction "CLK_OUT_40") (pintype "output+no_connect"))
    )
    (net (code "68") (name "unconnected-(U1200-JTAG_CLK{slash}TX_ER-Pad21)") (class "Default")
      (node (ref "U1200") (pin "21") (pinfunction "JTAG_CLK/TX_ER_21") (pintype "input+no_connect"))
    )
    (net (code "69") (name "unconnected-(U1200-JTAG_TDI{slash}SD-Pad24)") (class "Default")
      (node (ref "U1200") (pin "24") (pinfunction "JTAG_TDI/SD_24") (pintype "input+no_connect"))
    )
    (net (code "70") (name "unconnected-(U1200-JTAG_TMS-Pad23)") (class "Default")
      (node (ref "U1200") (pin "23") (pinfunction "JTAG_TMS_23") (pintype "input+no_connect"))
    )
    (net (code "71") (name "unconnected-(U1200-SIN-Pad17)") (class "Default")
      (node (ref "U1200") (pin "17") (pinfunction "SIN_17") (pintype "input+no_connect"))
    )
    (net (code "72") (name "unconnected-(U1200-SIP-Pad16)") (class "Default")
      (node (ref "U1200") (pin "16") (pinfunction "SIP_16") (pintype "input+no_connect"))
    )
    (net (code "73") (name "unconnected-(U1200-SON-Pad14)") (class "Default")
      (node (ref "U1200") (pin "14") (pinfunction "SON_14") (pintype "output+no_connect"))
    )
    (net (code "74") (name "unconnected-(U1200-SOP-Pad15)") (class "Default")
      (node (ref "U1200") (pin "15") (pinfunction "SOP_15") (pintype "output+no_connect"))
    )
    (net (code "75") (name "unconnected-(U1200-VDDA1P8_1-Pad13)") (class "Default")
      (node (ref "U1200") (pin "13") (pinfunction "VDDA1P8_1_13") (pintype "power_in+no_connect"))
    )
    (net (code "76") (name "unconnected-(U1200-VDDA1P8_2-Pad48)") (class "Default")
      (node (ref "U1200") (pin "48") (pinfunction "VDDA1P8_2_48") (pintype "power_in+no_connect"))
    )
    (net (code "77") (name "unconnected-(U1200-XO-Pad19)") (class "Default")
      (node (ref "U1200") (pin "19") (pinfunction "XO_19") (pintype "output+no_connect"))
    )
  )
)
